# icbm_control.net
KiCad netlist of a schematic drawn in EAGLE
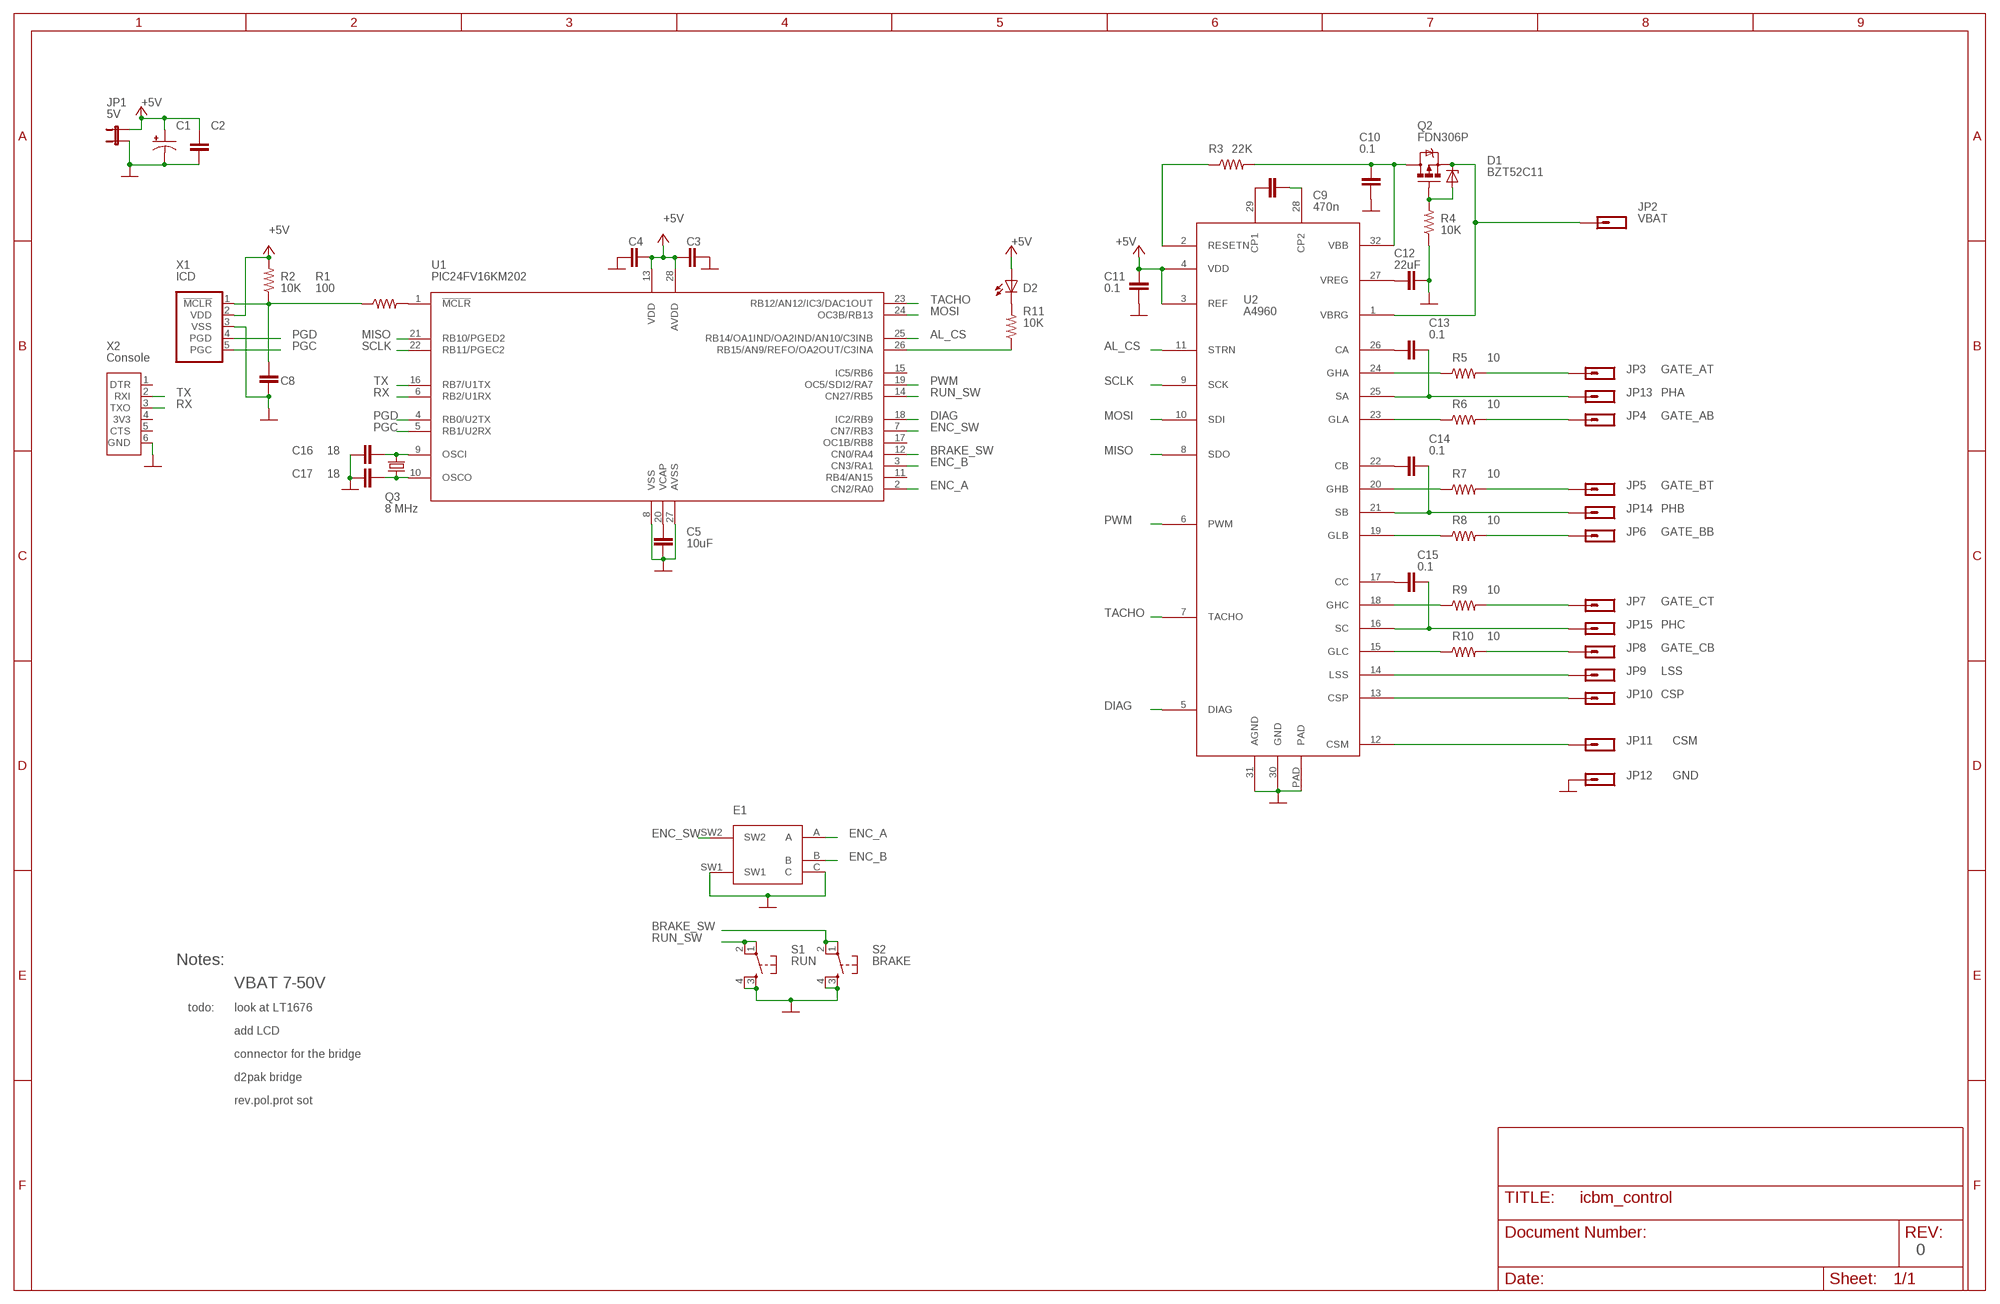
[diagram p0: schematic, sheet 1]

(export (version "E")
  (design (tool "Eeschema 10.0.6"))
  (components
    (comp (ref "C1")
      (value "CAP_POL-RAD8-TT")
      (footprint "eagle-import:CAP_RAD_8MM_TT")
      (libsource (lib "eagle-import") (part "CAP_POL-RAD8-TT"))
    )
    (comp (ref "C2")
      (value "CAP0603")
      (footprint "eagle-import:0603")
      (libsource (lib "eagle-import") (part "CAP0603"))
    )
    (comp (ref "C3")
      (value "0.1uF")
      (footprint "eagle-import:0603")
      (libsource (lib "eagle-import") (part "C-0603"))
    )
    (comp (ref "C4")
      (value "0.1uF")
      (footprint "eagle-import:0603")
      (libsource (lib "eagle-import") (part "C-0603"))
    )
    (comp (ref "C5")
      (value "10uF")
      (footprint "eagle-import:0603")
      (libsource (lib "eagle-import") (part "C-0603"))
    )
    (comp (ref "C8")
      (value "0.1uF")
      (footprint "eagle-import:0603")
      (libsource (lib "eagle-import") (part "C-0603"))
    )
    (comp (ref "C9")
      (value "470n")
      (footprint "eagle-import:0603")
      (libsource (lib "eagle-import") (part "C-0603"))
    )
    (comp (ref "C10")
      (value "0.1")
      (footprint "eagle-import:0603")
      (libsource (lib "eagle-import") (part "C-0603"))
    )
    (comp (ref "C11")
      (value "0.1")
      (footprint "eagle-import:0603")
      (libsource (lib "eagle-import") (part "C-0603"))
    )
    (comp (ref "C12")
      (value "22uF")
      (footprint "eagle-import:1206")
      (libsource (lib "eagle-import") (part "CAP1206"))
    )
    (comp (ref "C13")
      (value "0.1")
      (footprint "eagle-import:0603")
      (libsource (lib "eagle-import") (part "C-0603"))
    )
    (comp (ref "C14")
      (value "0.1")
      (footprint "eagle-import:0603")
      (libsource (lib "eagle-import") (part "C-0603"))
    )
    (comp (ref "C15")
      (value "0.1")
      (footprint "eagle-import:0603")
      (libsource (lib "eagle-import") (part "C-0603"))
    )
    (comp (ref "C16")
      (value "18")
      (footprint "eagle-import:0603")
      (libsource (lib "eagle-import") (part "C-0603"))
    )
    (comp (ref "C17")
      (value "18")
      (footprint "eagle-import:0603")
      (libsource (lib "eagle-import") (part "C-0603"))
    )
    (comp (ref "D1")
      (value "BZT52C11")
      (footprint "eagle-import:SOD-123")
      (libsource (lib "eagle-import") (part "ZENER-SOD-123"))
    )
    (comp (ref "D2")
      (value "LED-TT")
      (footprint "eagle-import:LED5MM_TT")
      (libsource (lib "eagle-import") (part "LED-TT"))
    )
    (comp (ref "E1")
      (value "ROTARY_ENCODER_SWITCH-LUT")
      (footprint "eagle-import:PEC12-LUT")
      (libsource (lib "eagle-import") (part "ROTARY_ENCODER_SWITCH-LUT"))
    )
    (comp (ref "JP1")
      (value "5V")
      (footprint "eagle-import:1X02-LUT")
      (libsource (lib "eagle-import") (part "JP1E-LUT"))
    )
    (comp (ref "JP2")
      (value "VBAT")
      (footprint "eagle-import:1X01_TT")
      (libsource (lib "eagle-import") (part "M01-TT"))
    )
    (comp (ref "JP3")
      (value "GATE_AT")
      (footprint "eagle-import:1X01_TT")
      (libsource (lib "eagle-import") (part "M01-TT"))
    )
    (comp (ref "JP4")
      (value "GATE_AB")
      (footprint "eagle-import:1X01_TT")
      (libsource (lib "eagle-import") (part "M01-TT"))
    )
    (comp (ref "JP5")
      (value "GATE_BT")
      (footprint "eagle-import:1X01_TT")
      (libsource (lib "eagle-import") (part "M01-TT"))
    )
    (comp (ref "JP6")
      (value "GATE_BB")
      (footprint "eagle-import:1X01_TT")
      (libsource (lib "eagle-import") (part "M01-TT"))
    )
    (comp (ref "JP7")
      (value "GATE_CT")
      (footprint "eagle-import:1X01_TT")
      (libsource (lib "eagle-import") (part "M01-TT"))
    )
    (comp (ref "JP8")
      (value "GATE_CB")
      (footprint "eagle-import:1X01_TT")
      (libsource (lib "eagle-import") (part "M01-TT"))
    )
    (comp (ref "JP9")
      (value "LSS")
      (footprint "eagle-import:1X01_TT")
      (libsource (lib "eagle-import") (part "M01-TT"))
    )
    (comp (ref "JP10")
      (value "CSP")
      (footprint "eagle-import:1X01_TT")
      (libsource (lib "eagle-import") (part "M01-TT"))
    )
    (comp (ref "JP11")
      (value "CSM")
      (footprint "eagle-import:1X01_TT")
      (libsource (lib "eagle-import") (part "M01-TT"))
    )
    (comp (ref "JP12")
      (value "GND")
      (footprint "eagle-import:1X01_TT")
      (libsource (lib "eagle-import") (part "M01-TT"))
    )
    (comp (ref "JP13")
      (value "PHA")
      (footprint "eagle-import:1X01_TT")
      (libsource (lib "eagle-import") (part "M01-TT"))
    )
    (comp (ref "JP14")
      (value "PHB")
      (footprint "eagle-import:1X01_TT")
      (libsource (lib "eagle-import") (part "M01-TT"))
    )
    (comp (ref "JP15")
      (value "PHC")
      (footprint "eagle-import:1X01_TT")
      (libsource (lib "eagle-import") (part "M01-TT"))
    )
    (comp (ref "Q2")
      (value "FDN306P")
      (footprint "eagle-import:DPAK")
      (libsource (lib "eagle-import") (part "MOSFET-PCHANNEL-DPAK"))
    )
    (comp (ref "Q3")
      (value "8 MHz")
      (footprint "eagle-import:HC49US_TT")
      (libsource (lib "eagle-import") (part "CRYSTAL_SFE-TT"))
    )
    (comp (ref "R1")
      (value "100")
      (footprint "eagle-import:0603")
      (libsource (lib "eagle-import") (part "RESISTOR-0603"))
    )
    (comp (ref "R2")
      (value "10K")
      (footprint "eagle-import:0603")
      (libsource (lib "eagle-import") (part "RESISTOR-0603"))
    )
    (comp (ref "R3")
      (value "22K")
      (footprint "eagle-import:0603")
      (libsource (lib "eagle-import") (part "RESISTOR-0603"))
    )
    (comp (ref "R4")
      (value "10K")
      (footprint "eagle-import:0603")
      (libsource (lib "eagle-import") (part "RESISTOR-0603"))
    )
    (comp (ref "R5")
      (value "10")
      (footprint "eagle-import:0603")
      (libsource (lib "eagle-import") (part "RESISTOR-0603"))
    )
    (comp (ref "R6")
      (value "10")
      (footprint "eagle-import:0603")
      (libsource (lib "eagle-import") (part "RESISTOR-0603"))
    )
    (comp (ref "R7")
      (value "10")
      (footprint "eagle-import:0603")
      (libsource (lib "eagle-import") (part "RESISTOR-0603"))
    )
    (comp (ref "R8")
      (value "10")
      (footprint "eagle-import:0603")
      (libsource (lib "eagle-import") (part "RESISTOR-0603"))
    )
    (comp (ref "R9")
      (value "10")
      (footprint "eagle-import:0603")
      (libsource (lib "eagle-import") (part "RESISTOR-0603"))
    )
    (comp (ref "R10")
      (value "10")
      (footprint "eagle-import:0603")
      (libsource (lib "eagle-import") (part "RESISTOR-0603"))
    )
    (comp (ref "R11")
      (value "10K")
      (footprint "eagle-import:0603")
      (libsource (lib "eagle-import") (part "RESISTOR-0603"))
    )
    (comp (ref "S1")
      (value "RUN")
      (footprint "eagle-import:TACT_PTH-LUT")
      (libsource (lib "eagle-import") (part "TAC_SWITCH-LUT"))
    )
    (comp (ref "S2")
      (value "BRAKE")
      (footprint "eagle-import:TACT_PTH-LUT")
      (libsource (lib "eagle-import") (part "TAC_SWITCH-LUT"))
    )
    (comp (ref "U1")
      (value "PIC24FV16KM202")
      (footprint "eagle-import:DIL28-3-TT")
      (libsource (lib "eagle-import") (part "PIC24FX16KM202-TT"))
    )
    (comp (ref "U2")
      (value "A4960")
      (footprint "eagle-import:LQPF-32")
      (libsource (lib "eagle-import") (part "A4960"))
    )
    (comp (ref "X1")
      (value "ICD")
      (footprint "eagle-import:1X05-TT")
      (libsource (lib "eagle-import") (part "PIC_ICD-TT"))
    )
    (comp (ref "X2")
      (value "Console")
      (footprint "eagle-import:1X06TT")
      (libsource (lib "eagle-import") (part "SERIAL-SFTT"))
    )
  )
  (nets
    (net (code "1") (name "+5V") (class "Default")
      (node (ref "C1") (pin "P") (pinfunction "+_P") (pintype "passive"))
      (node (ref "C11") (pin "2") (pinfunction "2_2") (pintype "passive"))
      (node (ref "C2") (pin "1") (pinfunction "1_1") (pintype "passive"))
      (node (ref "C3") (pin "1") (pinfunction "1_1") (pintype "passive"))
      (node (ref "C4") (pin "2") (pinfunction "2_2") (pintype "passive"))
      (node (ref "D2") (pin "A") (pinfunction "A_A") (pintype "passive"))
      (node (ref "JP1") (pin "2") (pinfunction "2_2") (pintype "passive"))
      (node (ref "R2") (pin "2") (pinfunction "2_2") (pintype "passive"))
      (node (ref "U1") (pin "13") (pinfunction "VDD_13") (pintype "bidirectional"))
      (node (ref "U1") (pin "28") (pinfunction "AVDD_28") (pintype "bidirectional"))
      (node (ref "U2") (pin "3") (pinfunction "REF_3") (pintype "bidirectional"))
      (node (ref "U2") (pin "4") (pinfunction "VDD_4") (pintype "bidirectional"))
      (node (ref "X1") (pin "2") (pinfunction "VDD_2") (pintype "passive"))
    )
    (net (code "2") (name "/AL_CS") (class "Default")
      (node (ref "U1") (pin "25") (pinfunction "RB14/OA1IND/OA2IND/AN10/C3INB_25") (pintype "bidirectional"))
      (node (ref "U2") (pin "11") (pinfunction "STRN_11") (pintype "bidirectional"))
    )
    (net (code "3") (name "/BRAKE_SW") (class "Default")
      (node (ref "S2") (pin "1") (pinfunction "1_1") (pintype "passive"))
      (node (ref "S2") (pin "2") (pinfunction "2_2") (pintype "passive"))
      (node (ref "U1") (pin "12") (pinfunction "CN0/RA4_12") (pintype "bidirectional"))
    )
    (net (code "4") (name "/DIAG") (class "Default")
      (node (ref "U1") (pin "18") (pinfunction "IC2/RB9_18") (pintype "bidirectional"))
      (node (ref "U2") (pin "5") (pinfunction "DIAG_5") (pintype "bidirectional"))
    )
    (net (code "5") (name "/ENC_A") (class "Default")
      (node (ref "E1") (pin "A") (pinfunction "A_A") (pintype "passive"))
      (node (ref "U1") (pin "2") (pinfunction "CN2/RA0_2") (pintype "bidirectional"))
    )
    (net (code "6") (name "/ENC_B") (class "Default")
      (node (ref "E1") (pin "B") (pinfunction "B_B") (pintype "passive"))
      (node (ref "U1") (pin "3") (pinfunction "CN3/RA1_3") (pintype "bidirectional"))
    )
    (net (code "7") (name "/ENC_SW") (class "Default")
      (node (ref "E1") (pin "SW2") (pinfunction "SW2_SW2") (pintype "passive"))
      (node (ref "U1") (pin "7") (pinfunction "CN7/RB3_7") (pintype "bidirectional"))
    )
    (net (code "8") (name "/MISO") (class "Default")
      (node (ref "U1") (pin "21") (pinfunction "RB10/PGED2_21") (pintype "bidirectional"))
      (node (ref "U2") (pin "8") (pinfunction "SDO_8") (pintype "bidirectional"))
    )
    (net (code "9") (name "/MOSI") (class "Default")
      (node (ref "U1") (pin "24") (pinfunction "OC3B/RB13_24") (pintype "bidirectional"))
      (node (ref "U2") (pin "10") (pinfunction "SDI_10") (pintype "bidirectional"))
    )
    (net (code "10") (name "/PGC") (class "Default")
      (node (ref "U1") (pin "5") (pinfunction "RB1/U2RX_5") (pintype "bidirectional"))
      (node (ref "X1") (pin "5") (pinfunction "PGC_5") (pintype "passive"))
    )
    (net (code "11") (name "/PGD") (class "Default")
      (node (ref "U1") (pin "4") (pinfunction "RB0/U2TX_4") (pintype "bidirectional"))
      (node (ref "X1") (pin "4") (pinfunction "PGD_4") (pintype "passive"))
    )
    (net (code "12") (name "/PWM") (class "Default")
      (node (ref "U1") (pin "19") (pinfunction "OC5/SDI2/RA7_19") (pintype "bidirectional"))
      (node (ref "U2") (pin "6") (pinfunction "PWM_6") (pintype "bidirectional"))
    )
    (net (code "13") (name "/RUN_SW") (class "Default")
      (node (ref "S1") (pin "1") (pinfunction "1_1") (pintype "passive"))
      (node (ref "S1") (pin "2") (pinfunction "2_2") (pintype "passive"))
      (node (ref "U1") (pin "14") (pinfunction "CN27/RB5_14") (pintype "bidirectional"))
    )
    (net (code "14") (name "/RX") (class "Default")
      (node (ref "U1") (pin "6") (pinfunction "RB2/U1RX_6") (pintype "bidirectional"))
      (node (ref "X2") (pin "3") (pinfunction "TXO_3") (pintype "bidirectional"))
    )
    (net (code "15") (name "/SCLK") (class "Default")
      (node (ref "U1") (pin "22") (pinfunction "RB11/PGEC2_22") (pintype "bidirectional"))
      (node (ref "U2") (pin "9") (pinfunction "SCK_9") (pintype "bidirectional"))
    )
    (net (code "16") (name "/TACHO") (class "Default")
      (node (ref "U1") (pin "23") (pinfunction "RB12/AN12/IC3/DAC1OUT_23") (pintype "bidirectional"))
      (node (ref "U2") (pin "7") (pinfunction "TACHO_7") (pintype "bidirectional"))
    )
    (net (code "17") (name "/TX") (class "Default")
      (node (ref "U1") (pin "16") (pinfunction "RB7/U1TX_16") (pintype "bidirectional"))
      (node (ref "X2") (pin "2") (pinfunction "RXI_2") (pintype "bidirectional"))
    )
    (net (code "18") (name "GND") (class "Default")
      (node (ref "C1") (pin "N") (pinfunction "-_N") (pintype "passive"))
      (node (ref "C10") (pin "1") (pinfunction "1_1") (pintype "passive"))
      (node (ref "C11") (pin "1") (pinfunction "1_1") (pintype "passive"))
      (node (ref "C12") (pin "2") (pinfunction "2_2") (pintype "passive"))
      (node (ref "C16") (pin "1") (pinfunction "1_1") (pintype "passive"))
      (node (ref "C17") (pin "1") (pinfunction "1_1") (pintype "passive"))
      (node (ref "C2") (pin "2") (pinfunction "2_2") (pintype "passive"))
      (node (ref "C3") (pin "2") (pinfunction "2_2") (pintype "passive"))
      (node (ref "C4") (pin "1") (pinfunction "1_1") (pintype "passive"))
      (node (ref "C5") (pin "2") (pinfunction "2_2") (pintype "passive"))
      (node (ref "C8") (pin "1") (pinfunction "1_1") (pintype "passive"))
      (node (ref "E1") (pin "C") (pinfunction "C_C") (pintype "passive"))
      (node (ref "E1") (pin "SW1") (pinfunction "SW1_SW1") (pintype "passive"))
      (node (ref "JP1") (pin "1") (pinfunction "1_1") (pintype "passive"))
      (node (ref "JP12") (pin "1") (pinfunction "1_1") (pintype "passive"))
      (node (ref "R4") (pin "1") (pinfunction "1_1") (pintype "passive"))
      (node (ref "S1") (pin "3") (pinfunction "3_3") (pintype "passive"))
      (node (ref "S1") (pin "4") (pinfunction "4_4") (pintype "passive"))
      (node (ref "S2") (pin "3") (pinfunction "3_3") (pintype "passive"))
      (node (ref "S2") (pin "4") (pinfunction "4_4") (pintype "passive"))
      (node (ref "U1") (pin "27") (pinfunction "AVSS_27") (pintype "bidirectional"))
      (node (ref "U1") (pin "8") (pinfunction "VSS_8") (pintype "bidirectional"))
      (node (ref "U2") (pin "30") (pinfunction "GND_30") (pintype "bidirectional"))
      (node (ref "U2") (pin "31") (pinfunction "AGND_31") (pintype "bidirectional"))
      (node (ref "U2") (pin "PAD") (pinfunction "PAD_PAD") (pintype "bidirectional"))
      (node (ref "X1") (pin "3") (pinfunction "VSS_3") (pintype "passive"))
      (node (ref "X2") (pin "6") (pinfunction "GND_6") (pintype "bidirectional"))
    )
    (net (code "19") (name "Net-(D1-C)") (class "Default")
      (node (ref "D1") (pin "K") (pinfunction "C_K") (pintype "passive"))
      (node (ref "JP2") (pin "1") (pinfunction "1_1") (pintype "passive"))
      (node (ref "Q2") (pin "3") (pinfunction "S_3") (pintype "passive"))
      (node (ref "U2") (pin "1") (pinfunction "VBRG_1") (pintype "bidirectional"))
    )
    (net (code "20") (name "Net-(D2-C)") (class "Default")
      (node (ref "D2") (pin "K") (pinfunction "C_K") (pintype "passive"))
      (node (ref "R11") (pin "2") (pinfunction "2_2") (pintype "passive"))
    )
    (net (code "21") (name "Net-(JP3-Pad1)") (class "Default")
      (node (ref "JP3") (pin "1") (pinfunction "1_1") (pintype "passive"))
      (node (ref "R5") (pin "2") (pinfunction "2_2") (pintype "passive"))
    )
    (net (code "22") (name "Net-(JP4-Pad1)") (class "Default")
      (node (ref "JP4") (pin "1") (pinfunction "1_1") (pintype "passive"))
      (node (ref "R6") (pin "2") (pinfunction "2_2") (pintype "passive"))
    )
    (net (code "23") (name "Net-(JP5-Pad1)") (class "Default")
      (node (ref "JP5") (pin "1") (pinfunction "1_1") (pintype "passive"))
      (node (ref "R7") (pin "2") (pinfunction "2_2") (pintype "passive"))
    )
    (net (code "24") (name "Net-(JP6-Pad1)") (class "Default")
      (node (ref "JP6") (pin "1") (pinfunction "1_1") (pintype "passive"))
      (node (ref "R8") (pin "2") (pinfunction "2_2") (pintype "passive"))
    )
    (net (code "25") (name "Net-(JP7-Pad1)") (class "Default")
      (node (ref "JP7") (pin "1") (pinfunction "1_1") (pintype "passive"))
      (node (ref "R9") (pin "2") (pinfunction "2_2") (pintype "passive"))
    )
    (net (code "26") (name "Net-(JP8-Pad1)") (class "Default")
      (node (ref "JP8") (pin "1") (pinfunction "1_1") (pintype "passive"))
      (node (ref "R10") (pin "2") (pinfunction "2_2") (pintype "passive"))
    )
    (net (code "27") (name "Net-(Q2-D)") (class "Default")
      (node (ref "C10") (pin "2") (pinfunction "2_2") (pintype "passive"))
      (node (ref "Q2") (pin "4") (pinfunction "D_4") (pintype "passive"))
      (node (ref "R3") (pin "2") (pinfunction "2_2") (pintype "passive"))
      (node (ref "U2") (pin "32") (pinfunction "VBB_32") (pintype "bidirectional"))
    )
    (net (code "28") (name "Net-(Q2-G)") (class "Default")
      (node (ref "D1") (pin "A") (pinfunction "A_A") (pintype "passive"))
      (node (ref "Q2") (pin "1") (pinfunction "G_1") (pintype "passive"))
      (node (ref "R4") (pin "2") (pinfunction "2_2") (pintype "passive"))
    )
    (net (code "29") (name "Net-(U1-OSCI)") (class "Default")
      (node (ref "C16") (pin "2") (pinfunction "2_2") (pintype "passive"))
      (node (ref "Q3") (pin "2") (pinfunction "2_2") (pintype "passive"))
      (node (ref "U1") (pin "9") (pinfunction "OSCI_9") (pintype "bidirectional"))
    )
    (net (code "30") (name "Net-(U1-OSCO)") (class "Default")
      (node (ref "C17") (pin "2") (pinfunction "2_2") (pintype "passive"))
      (node (ref "Q3") (pin "1") (pinfunction "1_1") (pintype "passive"))
      (node (ref "U1") (pin "10") (pinfunction "OSCO_10") (pintype "bidirectional"))
    )
    (net (code "31") (name "Net-(U1-RB15{slash}AN9{slash}REFO{slash}OA2OUT{slash}C3INA)") (class "Default")
      (node (ref "R11") (pin "1") (pinfunction "1_1") (pintype "passive"))
      (node (ref "U1") (pin "26") (pinfunction "RB15/AN9/REFO/OA2OUT/C3INA_26") (pintype "bidirectional"))
    )
    (net (code "32") (name "Net-(U1-VCAP)") (class "Default")
      (node (ref "C5") (pin "1") (pinfunction "1_1") (pintype "passive"))
      (node (ref "U1") (pin "20") (pinfunction "VCAP_20") (pintype "bidirectional"))
    )
    (net (code "33") (name "Net-(U1-~{MCLR})") (class "Default")
      (node (ref "R1") (pin "2") (pinfunction "2_2") (pintype "passive"))
      (node (ref "U1") (pin "1") (pinfunction "~{MCLR}_1") (pintype "bidirectional"))
    )
    (net (code "34") (name "Net-(U2-CA)") (class "Default")
      (node (ref "C13") (pin "2") (pinfunction "2_2") (pintype "passive"))
      (node (ref "U2") (pin "26") (pinfunction "CA_26") (pintype "bidirectional"))
    )
    (net (code "35") (name "Net-(U2-CB)") (class "Default")
      (node (ref "C14") (pin "2") (pinfunction "2_2") (pintype "passive"))
      (node (ref "U2") (pin "22") (pinfunction "CB_22") (pintype "bidirectional"))
    )
    (net (code "36") (name "Net-(U2-CC)") (class "Default")
      (node (ref "C15") (pin "2") (pinfunction "2_2") (pintype "passive"))
      (node (ref "U2") (pin "17") (pinfunction "CC_17") (pintype "bidirectional"))
    )
    (net (code "37") (name "Net-(U2-CP1)") (class "Default")
      (node (ref "C9") (pin "1") (pinfunction "1_1") (pintype "passive"))
      (node (ref "U2") (pin "29") (pinfunction "CP1_29") (pintype "bidirectional"))
    )
    (net (code "38") (name "Net-(U2-CP2)") (class "Default")
      (node (ref "C9") (pin "2") (pinfunction "2_2") (pintype "passive"))
      (node (ref "U2") (pin "28") (pinfunction "CP2_28") (pintype "bidirectional"))
    )
    (net (code "39") (name "Net-(U2-CSM)") (class "Default")
      (node (ref "JP11") (pin "1") (pinfunction "1_1") (pintype "passive"))
      (node (ref "U2") (pin "12") (pinfunction "CSM_12") (pintype "bidirectional"))
    )
    (net (code "40") (name "Net-(U2-CSP)") (class "Default")
      (node (ref "JP10") (pin "1") (pinfunction "1_1") (pintype "passive"))
      (node (ref "U2") (pin "13") (pinfunction "CSP_13") (pintype "bidirectional"))
    )
    (net (code "41") (name "Net-(U2-GHA)") (class "Default")
      (node (ref "R5") (pin "1") (pinfunction "1_1") (pintype "passive"))
      (node (ref "U2") (pin "24") (pinfunction "GHA_24") (pintype "bidirectional"))
    )
    (net (code "42") (name "Net-(U2-GHB)") (class "Default")
      (node (ref "R7") (pin "1") (pinfunction "1_1") (pintype "passive"))
      (node (ref "U2") (pin "20") (pinfunction "GHB_20") (pintype "bidirectional"))
    )
    (net (code "43") (name "Net-(U2-GHC)") (class "Default")
      (node (ref "R9") (pin "1") (pinfunction "1_1") (pintype "passive"))
      (node (ref "U2") (pin "18") (pinfunction "GHC_18") (pintype "bidirectional"))
    )
    (net (code "44") (name "Net-(U2-GLA)") (class "Default")
      (node (ref "R6") (pin "1") (pinfunction "1_1") (pintype "passive"))
      (node (ref "U2") (pin "23") (pinfunction "GLA_23") (pintype "bidirectional"))
    )
    (net (code "45") (name "Net-(U2-GLB)") (class "Default")
      (node (ref "R8") (pin "1") (pinfunction "1_1") (pintype "passive"))
      (node (ref "U2") (pin "19") (pinfunction "GLB_19") (pintype "bidirectional"))
    )
    (net (code "46") (name "Net-(U2-GLC)") (class "Default")
      (node (ref "R10") (pin "1") (pinfunction "1_1") (pintype "passive"))
      (node (ref "U2") (pin "15") (pinfunction "GLC_15") (pintype "bidirectional"))
    )
    (net (code "47") (name "Net-(U2-LSS)") (class "Default")
      (node (ref "JP9") (pin "1") (pinfunction "1_1") (pintype "passive"))
      (node (ref "U2") (pin "14") (pinfunction "LSS_14") (pintype "bidirectional"))
    )
    (net (code "48") (name "Net-(U2-RESETN)") (class "Default")
      (node (ref "R3") (pin "1") (pinfunction "1_1") (pintype "passive"))
      (node (ref "U2") (pin "2") (pinfunction "RESETN_2") (pintype "bidirectional"))
    )
    (net (code "49") (name "Net-(U2-SA)") (class "Default")
      (node (ref "C13") (pin "1") (pinfunction "1_1") (pintype "passive"))
      (node (ref "JP13") (pin "1") (pinfunction "1_1") (pintype "passive"))
      (node (ref "U2") (pin "25") (pinfunction "SA_25") (pintype "bidirectional"))
    )
    (net (code "50") (name "Net-(U2-SB)") (class "Default")
      (node (ref "C14") (pin "1") (pinfunction "1_1") (pintype "passive"))
      (node (ref "JP14") (pin "1") (pinfunction "1_1") (pintype "passive"))
      (node (ref "U2") (pin "21") (pinfunction "SB_21") (pintype "bidirectional"))
    )
    (net (code "51") (name "Net-(U2-SC)") (class "Default")
      (node (ref "C15") (pin "1") (pinfunction "1_1") (pintype "passive"))
      (node (ref "JP15") (pin "1") (pinfunction "1_1") (pintype "passive"))
      (node (ref "U2") (pin "16") (pinfunction "SC_16") (pintype "bidirectional"))
    )
    (net (code "52") (name "Net-(U2-VREG)") (class "Default")
      (node (ref "C12") (pin "1") (pinfunction "1_1") (pintype "passive"))
      (node (ref "U2") (pin "27") (pinfunction "VREG_27") (pintype "bidirectional"))
    )
    (net (code "53") (name "Net-(X1-~{MCLR})") (class "Default")
      (node (ref "C8") (pin "2") (pinfunction "2_2") (pintype "passive"))
      (node (ref "R1") (pin "1") (pinfunction "1_1") (pintype "passive"))
      (node (ref "R2") (pin "1") (pinfunction "1_1") (pintype "passive"))
      (node (ref "X1") (pin "1") (pinfunction "~{MCLR}_1") (pintype "passive"))
    )
    (net (code "54") (name "unconnected-(U1-IC5{slash}RB6-Pad15)") (class "Default")
      (node (ref "U1") (pin "15") (pinfunction "IC5/RB6_15") (pintype "bidirectional"))
    )
    (net (code "55") (name "unconnected-(U1-OC1B{slash}RB8-Pad17)") (class "Default")
      (node (ref "U1") (pin "17") (pinfunction "OC1B/RB8_17") (pintype "bidirectional"))
    )
    (net (code "56") (name "unconnected-(U1-RB4{slash}AN15-Pad11)") (class "Default")
      (node (ref "U1") (pin "11") (pinfunction "RB4/AN15_11") (pintype "bidirectional"))
    )
    (net (code "57") (name "unconnected-(X2-3V3-Pad4)") (class "Default")
      (node (ref "X2") (pin "4") (pinfunction "3V3_4") (pintype "bidirectional"))
    )
    (net (code "58") (name "unconnected-(X2-CTS-Pad5)") (class "Default")
      (node (ref "X2") (pin "5") (pinfunction "CTS_5") (pintype "bidirectional"))
    )
    (net (code "59") (name "unconnected-(X2-DTR-Pad1)") (class "Default")
      (node (ref "X2") (pin "1") (pinfunction "DTR_1") (pintype "bidirectional"))
    )
  )
)
